# switch-2layer.net
KiCad netlist of a schematic drawn in EAGLE
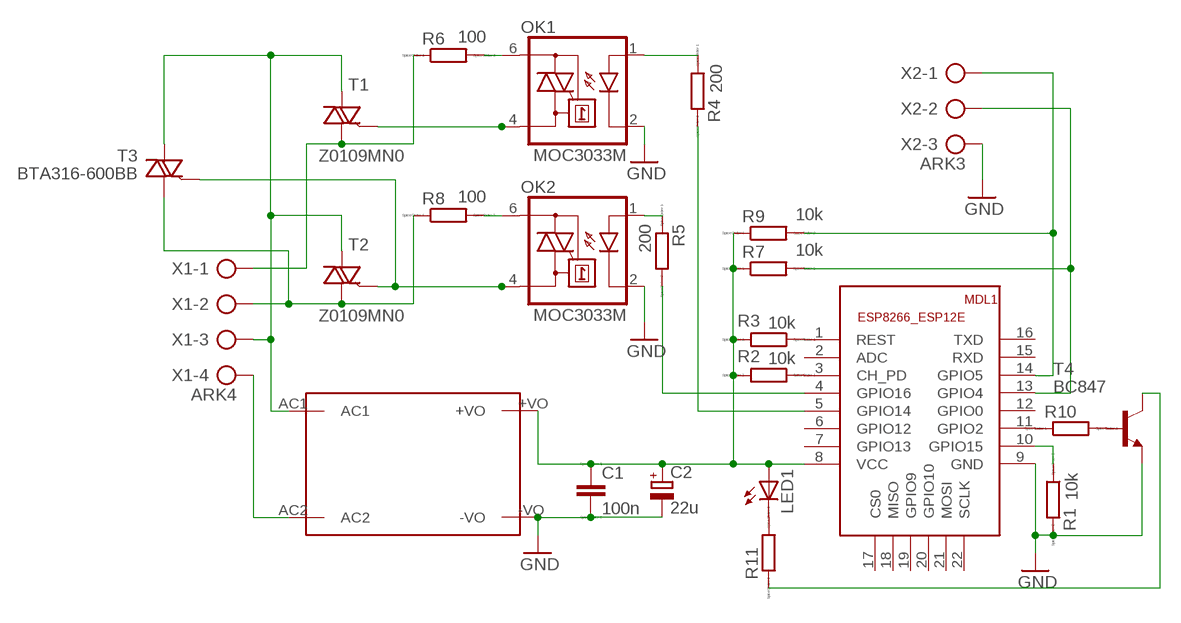
[diagram p0: schematic, sheet 1]

(export (version "E")
  (design (tool "Eeschema 10.0.6"))
  (components
    (comp (ref "C1")
      (value "100n")
      (footprint "eagle-import:C1206")
      (libsource (lib "eagle-import") (part "CC1206"))
    )
    (comp (ref "C2")
      (value "22u")
      (footprint "eagle-import:E2,5-6")
      (libsource (lib "eagle-import") (part "CPOL-EUE2.5-6"))
    )
    (comp (ref "LED1")
      (value "LEDSMT1206")
      (footprint "eagle-import:1206")
      (libsource (lib "eagle-import") (part "LEDSMT1206"))
    )
    (comp (ref "MDL1")
      (value "ESP12-F")
      (footprint "eagle-import:ESP8266-ESP12E")
      (libsource (lib "eagle-import") (part "ESP8266-12EESP8266-ESP12E"))
    )
    (comp (ref "OK1")
      (value "MOC3033M")
      (footprint "eagle-import:DIL06")
      (fields (field (name "MF") "FAIRCHILD SEMICONDUCTOR") (field (name "MPN") "MOC3033-M"))
      (libsource (lib "eagle-import") (part "MOC3033M"))
    )
    (comp (ref "OK2")
      (value "MOC3033M")
      (footprint "eagle-import:DIL06")
      (fields (field (name "MF") "FAIRCHILD SEMICONDUCTOR") (field (name "MPN") "MOC3033-M"))
      (libsource (lib "eagle-import") (part "MOC3033M"))
    )
    (comp (ref "R1")
      (value "10k")
      (footprint "eagle-import:R1206")
      (libsource (lib "eagle-import") (part "RR1206"))
    )
    (comp (ref "R2")
      (value "10k")
      (footprint "eagle-import:R1206")
      (libsource (lib "eagle-import") (part "RR1206"))
    )
    (comp (ref "R3")
      (value "10k")
      (footprint "eagle-import:R1206")
      (libsource (lib "eagle-import") (part "RR1206"))
    )
    (comp (ref "R4")
      (value "200")
      (footprint "eagle-import:R1206")
      (libsource (lib "eagle-import") (part "RR1206"))
    )
    (comp (ref "R5")
      (value "200")
      (footprint "eagle-import:R1206")
      (libsource (lib "eagle-import") (part "RR1206"))
    )
    (comp (ref "R6")
      (value "100")
      (footprint "eagle-import:R1206")
      (libsource (lib "eagle-import") (part "RR1206"))
    )
    (comp (ref "R7")
      (value "10k")
      (footprint "eagle-import:R1206")
      (libsource (lib "eagle-import") (part "RR1206"))
    )
    (comp (ref "R8")
      (value "100")
      (footprint "eagle-import:R1206")
      (libsource (lib "eagle-import") (part "RR1206"))
    )
    (comp (ref "R9")
      (value "10k")
      (footprint "eagle-import:R1206")
      (libsource (lib "eagle-import") (part "RR1206"))
    )
    (comp (ref "R10")
      (value "RR1206")
      (footprint "eagle-import:R1206")
      (libsource (lib "eagle-import") (part "RR1206"))
    )
    (comp (ref "R11")
      (value "RR1206")
      (footprint "eagle-import:R1206")
      (libsource (lib "eagle-import") (part "RR1206"))
    )
    (comp (ref "T1")
      (value "Z0109MN0")
      (footprint "eagle-import:SOT223")
      (libsource (lib "eagle-import") (part "Z0109MN0"))
    )
    (comp (ref "T2")
      (value "Z0109MN0")
      (footprint "eagle-import:SOT223")
      (libsource (lib "eagle-import") (part "Z0109MN0"))
    )
    (comp (ref "T3")
      (value "BTA316-600BB")
      (footprint "eagle-import:SOT404")
      (libsource (lib "eagle-import") (part "BTA316B-600B"))
    )
    (comp (ref "T4")
      (value "BC847")
      (footprint "eagle-import:SOT23")
      (libsource (lib "eagle-import") (part "BC847"))
    )
    (comp (ref "U$1")
      (value "HLK-PM03")
      (footprint "eagle-import:HLK-PM03")
      (libsource (lib "eagle-import") (part "HLK-PM03"))
    )
    (comp (ref "X1")
      (value "ARK4")
      (footprint "eagle-import:AK500_4")
      (libsource (lib "eagle-import") (part "AK500/4"))
    )
    (comp (ref "X2")
      (value "ARK3")
      (footprint "eagle-import:AK500_3")
      (libsource (lib "eagle-import") (part "AK500/3"))
    )
  )
  (nets
    (net (code "1") (name "GND") (class "Default")
      (node (ref "C1") (pin "2") (pinfunction "2_2") (pintype "passive"))
      (node (ref "C2") (pin "-") (pinfunction "-_-") (pintype "passive"))
      (node (ref "MDL1") (pin "9") (pinfunction "GND_9") (pintype "bidirectional"))
      (node (ref "OK1") (pin "2") (pinfunction "C_2") (pintype "passive"))
      (node (ref "OK2") (pin "2") (pinfunction "C_2") (pintype "passive"))
      (node (ref "R1") (pin "2") (pinfunction "2_2") (pintype "passive"))
      (node (ref "T4") (pin "2") (pinfunction "E_2") (pintype "passive"))
      (node (ref "U$1") (pin "-VO") (pinfunction "-VO_-VO") (pintype "bidirectional"))
      (node (ref "X2") (pin "3") (pinfunction "KL_3") (pintype "passive"))
    )
    (net (code "2") (name "Net-(LED1-PadC)") (class "Default")
      (node (ref "LED1") (pin "C") (pinfunction "C_C") (pintype "passive"))
      (node (ref "R11") (pin "2") (pinfunction "2_2") (pintype "passive"))
    )
    (net (code "3") (name "Net-(MDL1-CH_PD)") (class "Default")
      (node (ref "MDL1") (pin "3") (pinfunction "CH_PD_3") (pintype "bidirectional"))
      (node (ref "R2") (pin "1") (pinfunction "1_1") (pintype "passive"))
    )
    (net (code "4") (name "Net-(MDL1-GPIO2)") (class "Default")
      (node (ref "MDL1") (pin "11") (pinfunction "GPIO2_11") (pintype "bidirectional"))
      (node (ref "R10") (pin "1") (pinfunction "1_1") (pintype "passive"))
    )
    (net (code "5") (name "Net-(MDL1-GPIO4)") (class "Default")
      (node (ref "MDL1") (pin "13") (pinfunction "GPIO4_13") (pintype "bidirectional"))
      (node (ref "R7") (pin "2") (pinfunction "2_2") (pintype "passive"))
      (node (ref "X2") (pin "2") (pinfunction "KL_2") (pintype "passive"))
    )
    (net (code "6") (name "Net-(MDL1-GPIO5)") (class "Default")
      (node (ref "MDL1") (pin "14") (pinfunction "GPIO5_14") (pintype "bidirectional"))
      (node (ref "R9") (pin "2") (pinfunction "2_2") (pintype "passive"))
      (node (ref "X2") (pin "1") (pinfunction "KL_1") (pintype "passive"))
    )
    (net (code "7") (name "Net-(MDL1-GPIO14)") (class "Default")
      (node (ref "MDL1") (pin "5") (pinfunction "GPIO14_5") (pintype "bidirectional"))
      (node (ref "R4") (pin "2") (pinfunction "2_2") (pintype "passive"))
    )
    (net (code "8") (name "Net-(MDL1-GPIO15)") (class "Default")
      (node (ref "MDL1") (pin "10") (pinfunction "GPIO15_10") (pintype "bidirectional"))
      (node (ref "R1") (pin "1") (pinfunction "1_1") (pintype "passive"))
    )
    (net (code "9") (name "Net-(MDL1-GPIO16)") (class "Default")
      (node (ref "MDL1") (pin "4") (pinfunction "GPIO16_4") (pintype "bidirectional"))
      (node (ref "R5") (pin "2") (pinfunction "2_2") (pintype "passive"))
    )
    (net (code "10") (name "Net-(MDL1-REST)") (class "Default")
      (node (ref "MDL1") (pin "1") (pinfunction "REST_1") (pintype "bidirectional"))
      (node (ref "R3") (pin "1") (pinfunction "1_1") (pintype "passive"))
    )
    (net (code "11") (name "Net-(MDL1-VCC)") (class "Default")
      (node (ref "C1") (pin "1") (pinfunction "1_1") (pintype "passive"))
      (node (ref "C2") (pin "+") (pinfunction "+_+") (pintype "passive"))
      (node (ref "LED1") (pin "A") (pinfunction "A_A") (pintype "passive"))
      (node (ref "MDL1") (pin "8") (pinfunction "VCC_8") (pintype "bidirectional"))
      (node (ref "R2") (pin "2") (pinfunction "2_2") (pintype "passive"))
      (node (ref "R3") (pin "2") (pinfunction "2_2") (pintype "passive"))
      (node (ref "R7") (pin "1") (pinfunction "1_1") (pintype "passive"))
      (node (ref "R9") (pin "1") (pinfunction "1_1") (pintype "passive"))
      (node (ref "U$1") (pin "+VO") (pinfunction "+VO_+VO") (pintype "bidirectional"))
    )
    (net (code "12") (name "Net-(OK1-A)") (class "Default")
      (node (ref "OK1") (pin "1") (pinfunction "A_1") (pintype "passive"))
      (node (ref "R4") (pin "1") (pinfunction "1_1") (pintype "passive"))
    )
    (net (code "13") (name "Net-(OK1-A1)") (class "Default")
      (node (ref "OK1") (pin "4") (pinfunction "A1_4") (pintype "passive"))
      (node (ref "T1") (pin "3") (pinfunction "G_3") (pintype "passive"))
    )
    (net (code "14") (name "Net-(OK1-A2)") (class "Default")
      (node (ref "OK1") (pin "6") (pinfunction "A2_6") (pintype "passive"))
      (node (ref "R6") (pin "2") (pinfunction "2_2") (pintype "passive"))
    )
    (net (code "15") (name "Net-(OK2-A)") (class "Default")
      (node (ref "OK2") (pin "1") (pinfunction "A_1") (pintype "passive"))
      (node (ref "R5") (pin "1") (pinfunction "1_1") (pintype "passive"))
    )
    (net (code "16") (name "Net-(OK2-A1)") (class "Default")
      (node (ref "OK2") (pin "4") (pinfunction "A1_4") (pintype "passive"))
      (node (ref "T2") (pin "3") (pinfunction "G_3") (pintype "passive"))
      (node (ref "T3") (pin "3") (pinfunction "G_3") (pintype "passive"))
    )
    (net (code "17") (name "Net-(OK2-A2)") (class "Default")
      (node (ref "OK2") (pin "6") (pinfunction "A2_6") (pintype "passive"))
      (node (ref "R8") (pin "2") (pinfunction "2_2") (pintype "passive"))
    )
    (net (code "18") (name "Net-(T1-LD)") (class "Default")
      (node (ref "T1") (pin "1") (pinfunction "LD_1") (pintype "passive"))
      (node (ref "T2") (pin "1") (pinfunction "LD_1") (pintype "passive"))
      (node (ref "T3") (pin "1") (pinfunction "LD_1") (pintype "passive"))
      (node (ref "U$1") (pin "AC1") (pinfunction "AC1_AC1") (pintype "bidirectional"))
      (node (ref "X1") (pin "3") (pinfunction "KL_3") (pintype "passive"))
    )
    (net (code "19") (name "Net-(T3-CM)") (class "Default")
      (node (ref "R8") (pin "1") (pinfunction "1_1") (pintype "passive"))
      (node (ref "T2") (pin "2") (pinfunction "CM_2") (pintype "passive"))
      (node (ref "T2") (pin "4") (pinfunction "CM_4") (pintype "passive"))
      (node (ref "T3") (pin "MB") (pinfunction "CM_MB") (pintype "passive"))
      (node (ref "X1") (pin "2") (pinfunction "KL_2") (pintype "passive"))
    )
    (net (code "20") (name "Net-(T4-B)") (class "Default")
      (node (ref "R10") (pin "2") (pinfunction "2_2") (pintype "passive"))
      (node (ref "T4") (pin "1") (pinfunction "B_1") (pintype "passive"))
    )
    (net (code "21") (name "Net-(T4-C)") (class "Default")
      (node (ref "R11") (pin "1") (pinfunction "1_1") (pintype "passive"))
      (node (ref "T4") (pin "3") (pinfunction "C_3") (pintype "passive"))
    )
    (net (code "22") (name "Net-(X1A-KL)") (class "Default")
      (node (ref "R6") (pin "1") (pinfunction "1_1") (pintype "passive"))
      (node (ref "T1") (pin "2") (pinfunction "CM_2") (pintype "passive"))
      (node (ref "T1") (pin "4") (pinfunction "CM_4") (pintype "passive"))
      (node (ref "X1") (pin "1") (pinfunction "KL_1") (pintype "passive"))
    )
    (net (code "23") (name "Net-(X1D-KL)") (class "Default")
      (node (ref "U$1") (pin "AC2") (pinfunction "AC2_AC2") (pintype "bidirectional"))
      (node (ref "X1") (pin "4") (pinfunction "KL_4") (pintype "passive"))
    )
    (net (code "24") (name "unconnected-(MDL1-ADC-Pad2)") (class "Default")
      (node (ref "MDL1") (pin "2") (pinfunction "ADC_2") (pintype "bidirectional"))
    )
    (net (code "25") (name "unconnected-(MDL1-CS0-Pad17)") (class "Default")
      (node (ref "MDL1") (pin "17") (pinfunction "CS0_17") (pintype "bidirectional"))
    )
    (net (code "26") (name "unconnected-(MDL1-GPIO0-Pad12)") (class "Default")
      (node (ref "MDL1") (pin "12") (pinfunction "GPIO0_12") (pintype "bidirectional"))
    )
    (net (code "27") (name "unconnected-(MDL1-GPIO9-Pad19)") (class "Default")
      (node (ref "MDL1") (pin "19") (pinfunction "GPIO9_19") (pintype "bidirectional"))
    )
    (net (code "28") (name "unconnected-(MDL1-GPIO10-Pad20)") (class "Default")
      (node (ref "MDL1") (pin "20") (pinfunction "GPIO10_20") (pintype "bidirectional"))
    )
    (net (code "29") (name "unconnected-(MDL1-GPIO12-Pad6)") (class "Default")
      (node (ref "MDL1") (pin "6") (pinfunction "GPIO12_6") (pintype "bidirectional"))
    )
    (net (code "30") (name "unconnected-(MDL1-GPIO13-Pad7)") (class "Default")
      (node (ref "MDL1") (pin "7") (pinfunction "GPIO13_7") (pintype "bidirectional"))
    )
    (net (code "31") (name "unconnected-(MDL1-MISO-Pad18)") (class "Default")
      (node (ref "MDL1") (pin "18") (pinfunction "MISO_18") (pintype "bidirectional"))
    )
    (net (code "32") (name "unconnected-(MDL1-MOSI-Pad21)") (class "Default")
      (node (ref "MDL1") (pin "21") (pinfunction "MOSI_21") (pintype "bidirectional"))
    )
    (net (code "33") (name "unconnected-(MDL1-RXD-Pad15)") (class "Default")
      (node (ref "MDL1") (pin "15") (pinfunction "RXD_15") (pintype "bidirectional"))
    )
    (net (code "34") (name "unconnected-(MDL1-SCLK-Pad22)") (class "Default")
      (node (ref "MDL1") (pin "22") (pinfunction "SCLK_22") (pintype "bidirectional"))
    )
    (net (code "35") (name "unconnected-(MDL1-TXD-Pad16)") (class "Default")
      (node (ref "MDL1") (pin "16") (pinfunction "TXD_16") (pintype "bidirectional"))
    )
  )
)
